# FubarStep_v11.net
KiCad netlist of a schematic drawn in EAGLE
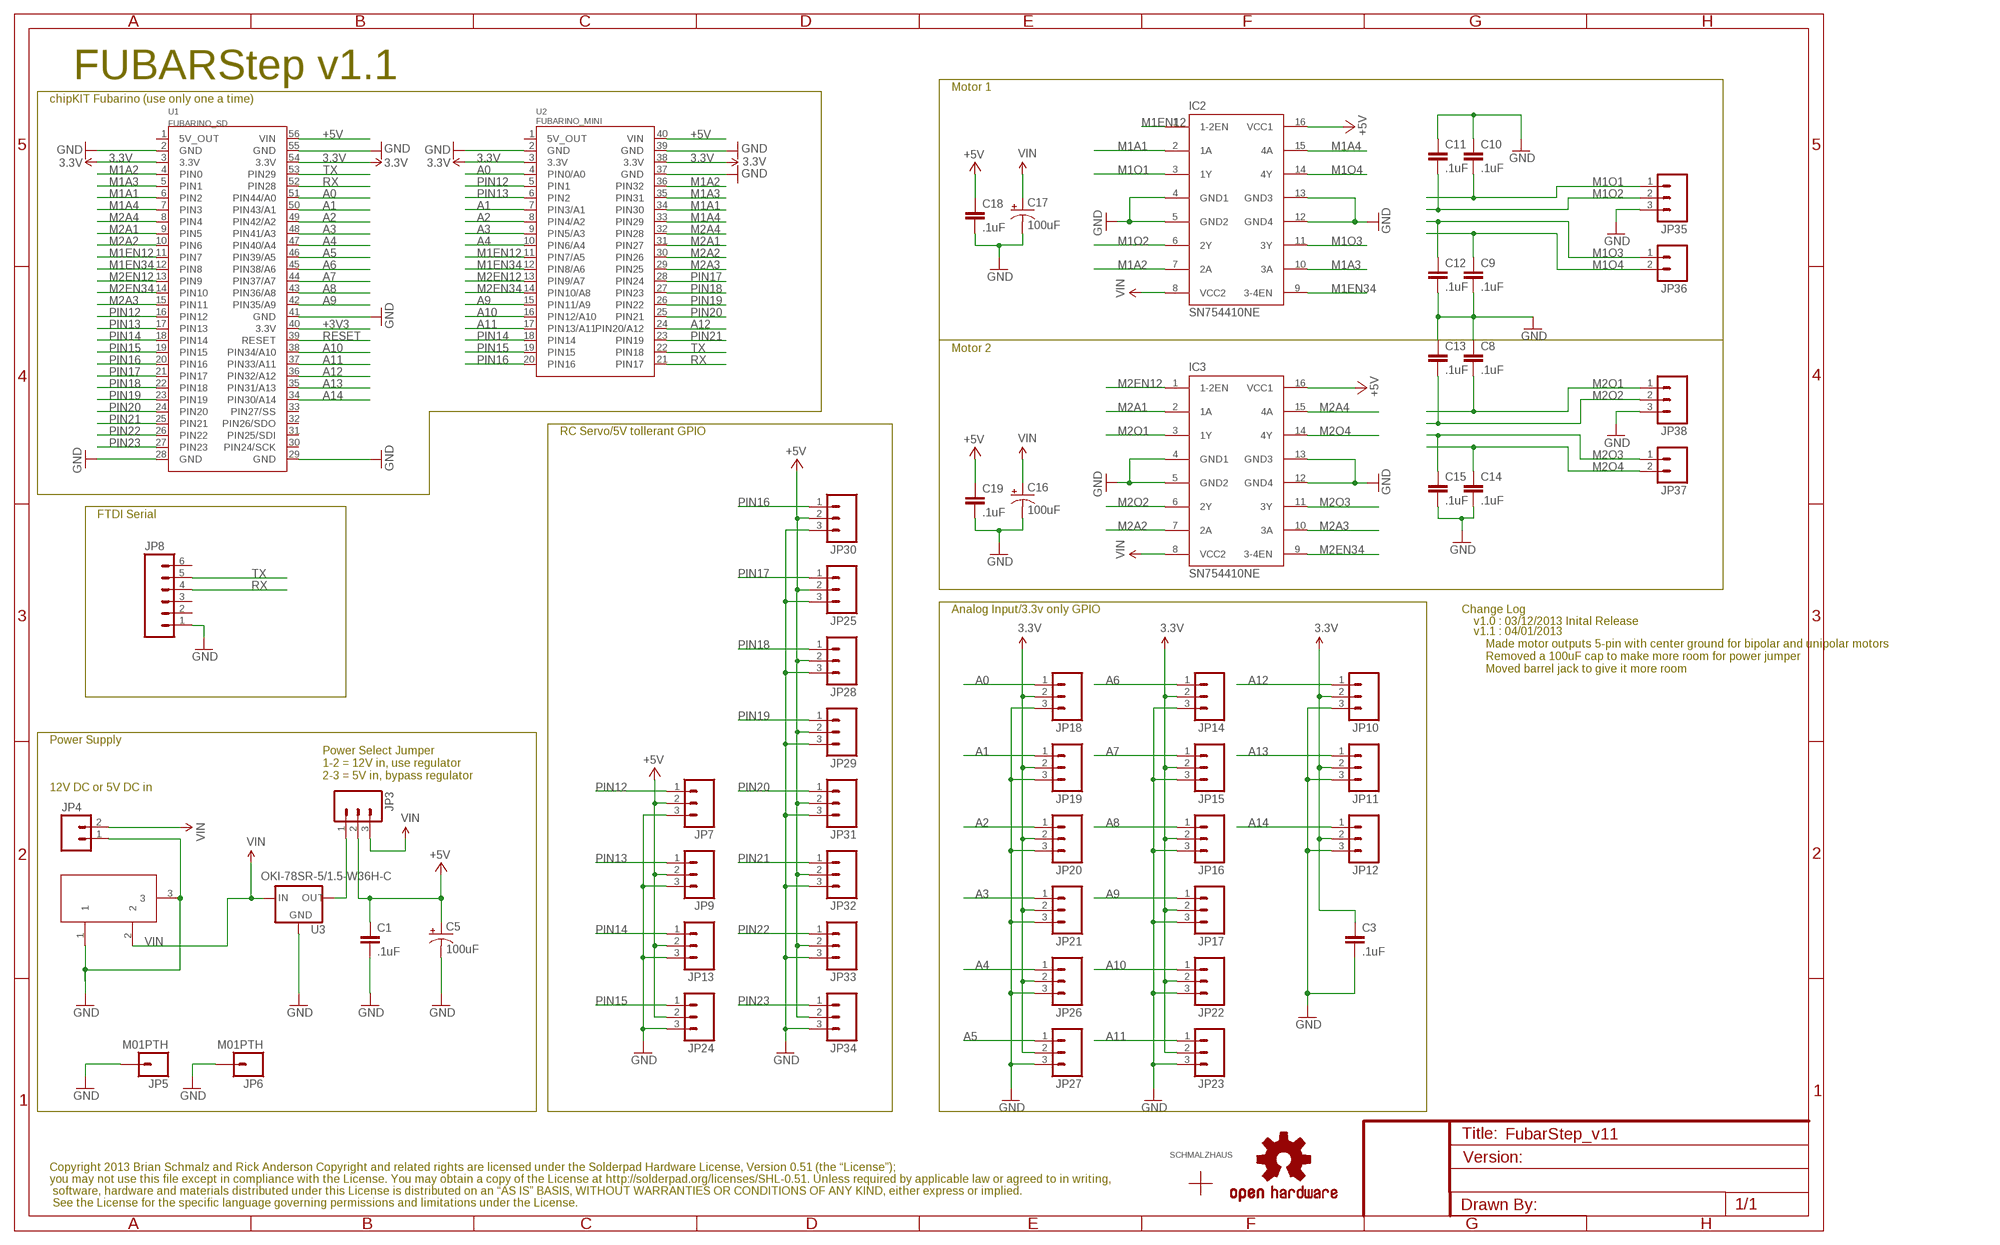
[diagram p0: schematic, sheet 1]

(export (version "E")
  (design (tool "Eeschema 10.0.6"))
  (components
    (comp (ref "C1")
      (value ".1uF")
      (footprint "eagle-import:CAP-PTH-SMALL")
      (libsource (lib "eagle-import") (part "CAPPTH"))
    )
    (comp (ref "C3")
      (value ".1uF")
      (footprint "eagle-import:CAP-PTH-SMALL")
      (libsource (lib "eagle-import") (part "CAPPTH"))
    )
    (comp (ref "C5")
      (value "100uF")
      (footprint "eagle-import:CPOL-RADIAL-100UF-25V")
      (libsource (lib "eagle-import") (part "CAP_POLPTH1"))
    )
    (comp (ref "C8")
      (value ".1uF")
      (footprint "eagle-import:CAP-PTH-SMALL")
      (libsource (lib "eagle-import") (part "CAPPTH"))
    )
    (comp (ref "C9")
      (value ".1uF")
      (footprint "eagle-import:CAP-PTH-SMALL")
      (libsource (lib "eagle-import") (part "CAPPTH"))
    )
    (comp (ref "C10")
      (value ".1uF")
      (footprint "eagle-import:CAP-PTH-SMALL")
      (libsource (lib "eagle-import") (part "CAPPTH"))
    )
    (comp (ref "C11")
      (value ".1uF")
      (footprint "eagle-import:CAP-PTH-SMALL")
      (libsource (lib "eagle-import") (part "CAPPTH"))
    )
    (comp (ref "C12")
      (value ".1uF")
      (footprint "eagle-import:CAP-PTH-SMALL")
      (libsource (lib "eagle-import") (part "CAPPTH"))
    )
    (comp (ref "C13")
      (value ".1uF")
      (footprint "eagle-import:CAP-PTH-SMALL")
      (libsource (lib "eagle-import") (part "CAPPTH"))
    )
    (comp (ref "C14")
      (value ".1uF")
      (footprint "eagle-import:CAP-PTH-SMALL")
      (libsource (lib "eagle-import") (part "CAPPTH"))
    )
    (comp (ref "C15")
      (value ".1uF")
      (footprint "eagle-import:CAP-PTH-SMALL")
      (libsource (lib "eagle-import") (part "CAPPTH"))
    )
    (comp (ref "C16")
      (value "100uF")
      (footprint "eagle-import:CPOL-RADIAL-100UF-25V")
      (libsource (lib "eagle-import") (part "CAP_POLPTH1"))
    )
    (comp (ref "C17")
      (value "100uF")
      (footprint "eagle-import:CPOL-RADIAL-100UF-25V")
      (libsource (lib "eagle-import") (part "CAP_POLPTH1"))
    )
    (comp (ref "C18")
      (value ".1uF")
      (footprint "eagle-import:CAP-PTH-SMALL")
      (libsource (lib "eagle-import") (part "CAPPTH"))
    )
    (comp (ref "C19")
      (value ".1uF")
      (footprint "eagle-import:CAP-PTH-SMALL")
      (libsource (lib "eagle-import") (part "CAPPTH"))
    )
    (comp (ref "IC2")
      (value "SN754410NE")
      (footprint "eagle-import:DIL16")
      (fields (field (name "MF") "Arrow Electronics") (field (name "MPN") "L293E"))
      (libsource (lib "eagle-import") (part "L293E"))
    )
    (comp (ref "IC3")
      (value "SN754410NE")
      (footprint "eagle-import:DIL16")
      (fields (field (name "MF") "Arrow Electronics") (field (name "MPN") "L293E"))
      (libsource (lib "eagle-import") (part "L293E"))
    )
    (comp (ref "JP3")
      (value "M03PTH")
      (footprint "eagle-import:1X03")
      (libsource (lib "eagle-import") (part "M03PTH"))
    )
    (comp (ref "JP4")
      (value "M023.5MM")
      (footprint "eagle-import:SCREWTERMINAL-3.5MM-2")
      (libsource (lib "eagle-import") (part "M023.5MM"))
    )
    (comp (ref "JP5")
      (value "M01PTH")
      (footprint "eagle-import:1X01")
      (libsource (lib "eagle-import") (part "M01PTH"))
    )
    (comp (ref "JP6")
      (value "M01PTH")
      (footprint "eagle-import:1X01")
      (libsource (lib "eagle-import") (part "M01PTH"))
    )
    (comp (ref "JP7")
      (value "M03PTH")
      (footprint "eagle-import:1X03")
      (libsource (lib "eagle-import") (part "M03PTH"))
    )
    (comp (ref "JP8")
      (value "M06LOCK")
      (footprint "eagle-import:1X06_LOCK")
      (libsource (lib "eagle-import") (part "M06LOCK"))
    )
    (comp (ref "JP9")
      (value "M03PTH")
      (footprint "eagle-import:1X03")
      (libsource (lib "eagle-import") (part "M03PTH"))
    )
    (comp (ref "JP10")
      (value "M03PTH")
      (footprint "eagle-import:1X03")
      (libsource (lib "eagle-import") (part "M03PTH"))
    )
    (comp (ref "JP11")
      (value "M03PTH")
      (footprint "eagle-import:1X03")
      (libsource (lib "eagle-import") (part "M03PTH"))
    )
    (comp (ref "JP12")
      (value "M03PTH")
      (footprint "eagle-import:1X03")
      (libsource (lib "eagle-import") (part "M03PTH"))
    )
    (comp (ref "JP13")
      (value "M03PTH")
      (footprint "eagle-import:1X03")
      (libsource (lib "eagle-import") (part "M03PTH"))
    )
    (comp (ref "JP14")
      (value "M03PTH")
      (footprint "eagle-import:1X03")
      (libsource (lib "eagle-import") (part "M03PTH"))
    )
    (comp (ref "JP15")
      (value "M03PTH")
      (footprint "eagle-import:1X03")
      (libsource (lib "eagle-import") (part "M03PTH"))
    )
    (comp (ref "JP16")
      (value "M03PTH")
      (footprint "eagle-import:1X03")
      (libsource (lib "eagle-import") (part "M03PTH"))
    )
    (comp (ref "JP17")
      (value "M03PTH")
      (footprint "eagle-import:1X03")
      (libsource (lib "eagle-import") (part "M03PTH"))
    )
    (comp (ref "JP18")
      (value "M03PTH")
      (footprint "eagle-import:1X03")
      (libsource (lib "eagle-import") (part "M03PTH"))
    )
    (comp (ref "JP19")
      (value "M03PTH")
      (footprint "eagle-import:1X03")
      (libsource (lib "eagle-import") (part "M03PTH"))
    )
    (comp (ref "JP20")
      (value "M03PTH")
      (footprint "eagle-import:1X03")
      (libsource (lib "eagle-import") (part "M03PTH"))
    )
    (comp (ref "JP21")
      (value "M03PTH")
      (footprint "eagle-import:1X03")
      (libsource (lib "eagle-import") (part "M03PTH"))
    )
    (comp (ref "JP22")
      (value "M03PTH")
      (footprint "eagle-import:1X03")
      (libsource (lib "eagle-import") (part "M03PTH"))
    )
    (comp (ref "JP23")
      (value "M03PTH")
      (footprint "eagle-import:1X03")
      (libsource (lib "eagle-import") (part "M03PTH"))
    )
    (comp (ref "JP24")
      (value "M03PTH")
      (footprint "eagle-import:1X03")
      (libsource (lib "eagle-import") (part "M03PTH"))
    )
    (comp (ref "JP25")
      (value "M03PTH")
      (footprint "eagle-import:1X03")
      (libsource (lib "eagle-import") (part "M03PTH"))
    )
    (comp (ref "JP26")
      (value "M03PTH")
      (footprint "eagle-import:1X03")
      (libsource (lib "eagle-import") (part "M03PTH"))
    )
    (comp (ref "JP27")
      (value "M03PTH")
      (footprint "eagle-import:1X03")
      (libsource (lib "eagle-import") (part "M03PTH"))
    )
    (comp (ref "JP28")
      (value "M03PTH")
      (footprint "eagle-import:1X03")
      (libsource (lib "eagle-import") (part "M03PTH"))
    )
    (comp (ref "JP29")
      (value "M03PTH")
      (footprint "eagle-import:1X03")
      (libsource (lib "eagle-import") (part "M03PTH"))
    )
    (comp (ref "JP30")
      (value "M03PTH")
      (footprint "eagle-import:1X03")
      (libsource (lib "eagle-import") (part "M03PTH"))
    )
    (comp (ref "JP31")
      (value "M03PTH")
      (footprint "eagle-import:1X03")
      (libsource (lib "eagle-import") (part "M03PTH"))
    )
    (comp (ref "JP32")
      (value "M03PTH")
      (footprint "eagle-import:1X03")
      (libsource (lib "eagle-import") (part "M03PTH"))
    )
    (comp (ref "JP33")
      (value "M03PTH")
      (footprint "eagle-import:1X03")
      (libsource (lib "eagle-import") (part "M03PTH"))
    )
    (comp (ref "JP34")
      (value "M03PTH")
      (footprint "eagle-import:1X03")
      (libsource (lib "eagle-import") (part "M03PTH"))
    )
    (comp (ref "JP35")
      (value "M03SCREW")
      (footprint "eagle-import:SCREWTERMINAL-3.5MM-3")
      (libsource (lib "eagle-import") (part "M03SCREW"))
    )
    (comp (ref "JP36")
      (value "M023.5MM")
      (footprint "eagle-import:SCREWTERMINAL-3.5MM-2")
      (libsource (lib "eagle-import") (part "M023.5MM"))
    )
    (comp (ref "JP37")
      (value "M023.5MM")
      (footprint "eagle-import:SCREWTERMINAL-3.5MM-2")
      (libsource (lib "eagle-import") (part "M023.5MM"))
    )
    (comp (ref "JP38")
      (value "M03SCREW")
      (footprint "eagle-import:SCREWTERMINAL-3.5MM-3")
      (libsource (lib "eagle-import") (part "M03SCREW"))
    )
    (comp (ref "LOGO1")
      (value "OSHW-LOGOM")
      (footprint "eagle-import:OSHW-LOGO-M")
      (libsource (lib "eagle-import") (part "OSHW-LOGOM"))
    )
    (comp (ref "U$1")
      (value "SCHMALZHAUSSCHMALZHAUS_SMALL")
      (footprint "eagle-import:SCHMALZHAUS_SMALL")
      (libsource (lib "eagle-import") (part "SCHMALZHAUSSCHMALZHAUS_SMALL"))
    )
    (comp (ref "U1")
      (value "FUBARINO_SD")
      (footprint "eagle-import:FUBARINO_SD")
      (libsource (lib "eagle-import") (part "FUBARINO_SD"))
    )
    (comp (ref "U2")
      (value "FUBARINO_MINI")
      (footprint "eagle-import:FUBARINO_MINI")
      (libsource (lib "eagle-import") (part "FUBARINO_MINI"))
    )
    (comp (ref "U3")
      (value "OKI-78SR-5/1.5-W36H-C")
      (footprint "eagle-import:TO220-IGO")
      (libsource (lib "eagle-import") (part "V_REG_78XXSINK"))
    )
    (comp (ref "X1")
      (value "DC21MMX")
      (footprint "eagle-import:DC-21MM")
      (libsource (lib "eagle-import") (part "DC21MMX"))
    )
  )
  (nets
    (net (code "1") (name "+5V") (class "Default")
      (node (ref "C1") (pin "1") (pinfunction "1_1") (pintype "passive"))
      (node (ref "C18") (pin "1") (pinfunction "1_1") (pintype "passive"))
      (node (ref "C19") (pin "1") (pinfunction "1_1") (pintype "passive"))
      (node (ref "C5") (pin "1") (pinfunction "+_1") (pintype "passive"))
      (node (ref "IC2") (pin "16") (pinfunction "VCC1_16") (pintype "power_in"))
      (node (ref "IC3") (pin "16") (pinfunction "VCC1_16") (pintype "power_in"))
      (node (ref "JP13") (pin "2") (pinfunction "2_2") (pintype "passive"))
      (node (ref "JP24") (pin "2") (pinfunction "2_2") (pintype "passive"))
      (node (ref "JP25") (pin "2") (pinfunction "2_2") (pintype "passive"))
      (node (ref "JP28") (pin "2") (pinfunction "2_2") (pintype "passive"))
      (node (ref "JP29") (pin "2") (pinfunction "2_2") (pintype "passive"))
      (node (ref "JP3") (pin "2") (pinfunction "2_2") (pintype "passive"))
      (node (ref "JP30") (pin "2") (pinfunction "2_2") (pintype "passive"))
      (node (ref "JP31") (pin "2") (pinfunction "2_2") (pintype "passive"))
      (node (ref "JP32") (pin "2") (pinfunction "2_2") (pintype "passive"))
      (node (ref "JP33") (pin "2") (pinfunction "2_2") (pintype "passive"))
      (node (ref "JP34") (pin "2") (pinfunction "2_2") (pintype "passive"))
      (node (ref "JP7") (pin "2") (pinfunction "2_2") (pintype "passive"))
      (node (ref "JP9") (pin "2") (pinfunction "2_2") (pintype "passive"))
      (node (ref "U1") (pin "56") (pinfunction "VIN_56") (pintype "bidirectional"))
      (node (ref "U2") (pin "40") (pinfunction "VIN_40") (pintype "bidirectional"))
    )
    (net (code "2") (name "/+3V3") (class "Default")
      (node (ref "U1") (pin "40") (pinfunction "3.3V_40") (pintype "bidirectional"))
    )
    (net (code "3") (name "/A0") (class "Default")
      (node (ref "JP18") (pin "1") (pinfunction "1_1") (pintype "passive"))
      (node (ref "U1") (pin "51") (pinfunction "PIN44/A0_51") (pintype "bidirectional"))
      (node (ref "U2") (pin "4") (pinfunction "PIN0/A0_4") (pintype "bidirectional"))
    )
    (net (code "4") (name "/A1") (class "Default")
      (node (ref "JP19") (pin "1") (pinfunction "1_1") (pintype "passive"))
      (node (ref "U1") (pin "50") (pinfunction "PIN43/A1_50") (pintype "bidirectional"))
      (node (ref "U2") (pin "7") (pinfunction "PIN3/A1_7") (pintype "bidirectional"))
    )
    (net (code "5") (name "/A2") (class "Default")
      (node (ref "JP20") (pin "1") (pinfunction "1_1") (pintype "passive"))
      (node (ref "U1") (pin "49") (pinfunction "PIN42/A2_49") (pintype "bidirectional"))
      (node (ref "U2") (pin "8") (pinfunction "PIN4/A2_8") (pintype "bidirectional"))
    )
    (net (code "6") (name "/A3") (class "Default")
      (node (ref "JP21") (pin "1") (pinfunction "1_1") (pintype "passive"))
      (node (ref "U1") (pin "48") (pinfunction "PIN41/A3_48") (pintype "bidirectional"))
      (node (ref "U2") (pin "9") (pinfunction "PIN5/A3_9") (pintype "bidirectional"))
    )
    (net (code "7") (name "/A4") (class "Default")
      (node (ref "JP26") (pin "1") (pinfunction "1_1") (pintype "passive"))
      (node (ref "U1") (pin "47") (pinfunction "PIN40/A4_47") (pintype "bidirectional"))
      (node (ref "U2") (pin "10") (pinfunction "PIN6/A4_10") (pintype "bidirectional"))
    )
    (net (code "8") (name "/A5") (class "Default")
      (node (ref "JP27") (pin "1") (pinfunction "1_1") (pintype "passive"))
      (node (ref "U1") (pin "46") (pinfunction "PIN39/A5_46") (pintype "bidirectional"))
    )
    (net (code "9") (name "/A6") (class "Default")
      (node (ref "JP14") (pin "1") (pinfunction "1_1") (pintype "passive"))
      (node (ref "U1") (pin "45") (pinfunction "PIN38/A6_45") (pintype "bidirectional"))
    )
    (net (code "10") (name "/A7") (class "Default")
      (node (ref "JP15") (pin "1") (pinfunction "1_1") (pintype "passive"))
      (node (ref "U1") (pin "44") (pinfunction "PIN37/A7_44") (pintype "bidirectional"))
    )
    (net (code "11") (name "/A8") (class "Default")
      (node (ref "JP16") (pin "1") (pinfunction "1_1") (pintype "passive"))
      (node (ref "U1") (pin "43") (pinfunction "PIN36/A8_43") (pintype "bidirectional"))
    )
    (net (code "12") (name "/A9") (class "Default")
      (node (ref "JP17") (pin "1") (pinfunction "1_1") (pintype "passive"))
      (node (ref "U1") (pin "42") (pinfunction "PIN35/A9_42") (pintype "bidirectional"))
      (node (ref "U2") (pin "15") (pinfunction "PIN11/A9_15") (pintype "bidirectional"))
    )
    (net (code "13") (name "/A10") (class "Default")
      (node (ref "JP22") (pin "1") (pinfunction "1_1") (pintype "passive"))
      (node (ref "U1") (pin "38") (pinfunction "PIN34/A10_38") (pintype "bidirectional"))
      (node (ref "U2") (pin "16") (pinfunction "PIN12/A10_16") (pintype "bidirectional"))
    )
    (net (code "14") (name "/A11") (class "Default")
      (node (ref "JP23") (pin "1") (pinfunction "1_1") (pintype "passive"))
      (node (ref "U1") (pin "37") (pinfunction "PIN33/A11_37") (pintype "bidirectional"))
      (node (ref "U2") (pin "17") (pinfunction "PIN13/A11_17") (pintype "bidirectional"))
    )
    (net (code "15") (name "/A12") (class "Default")
      (node (ref "JP10") (pin "1") (pinfunction "1_1") (pintype "passive"))
      (node (ref "U1") (pin "36") (pinfunction "PIN32/A12_36") (pintype "bidirectional"))
      (node (ref "U2") (pin "24") (pinfunction "PIN20/A12_24") (pintype "bidirectional"))
    )
    (net (code "16") (name "/A13") (class "Default")
      (node (ref "JP11") (pin "1") (pinfunction "1_1") (pintype "passive"))
      (node (ref "U1") (pin "35") (pinfunction "PIN31/A13_35") (pintype "bidirectional"))
    )
    (net (code "17") (name "/A14") (class "Default")
      (node (ref "JP12") (pin "1") (pinfunction "1_1") (pintype "passive"))
      (node (ref "U1") (pin "34") (pinfunction "PIN30/A14_34") (pintype "bidirectional"))
    )
    (net (code "18") (name "/M1A1") (class "Default")
      (node (ref "IC2") (pin "2") (pinfunction "1A_2") (pintype "input"))
      (node (ref "U1") (pin "6") (pinfunction "PIN2_6") (pintype "bidirectional"))
      (node (ref "U2") (pin "34") (pinfunction "PIN30_34") (pintype "bidirectional"))
    )
    (net (code "19") (name "/M1A2") (class "Default")
      (node (ref "IC2") (pin "7") (pinfunction "2A_7") (pintype "input"))
      (node (ref "U1") (pin "4") (pinfunction "PIN0_4") (pintype "bidirectional"))
      (node (ref "U2") (pin "36") (pinfunction "PIN32_36") (pintype "bidirectional"))
    )
    (net (code "20") (name "/M1A3") (class "Default")
      (node (ref "IC2") (pin "10") (pinfunction "3A_10") (pintype "input"))
      (node (ref "U1") (pin "5") (pinfunction "PIN1_5") (pintype "bidirectional"))
      (node (ref "U2") (pin "35") (pinfunction "PIN31_35") (pintype "bidirectional"))
    )
    (net (code "21") (name "/M1A4") (class "Default")
      (node (ref "IC2") (pin "15") (pinfunction "4A_15") (pintype "input"))
      (node (ref "U1") (pin "7") (pinfunction "PIN3_7") (pintype "bidirectional"))
      (node (ref "U2") (pin "33") (pinfunction "PIN29_33") (pintype "bidirectional"))
    )
    (net (code "22") (name "/M1EN12") (class "Default")
      (node (ref "IC2") (pin "1") (pinfunction "1-2EN_1") (pintype "input"))
      (node (ref "U1") (pin "11") (pinfunction "PIN7_11") (pintype "bidirectional"))
      (node (ref "U2") (pin "11") (pinfunction "PIN7/A5_11") (pintype "bidirectional"))
    )
    (net (code "23") (name "/M1EN34") (class "Default")
      (node (ref "IC2") (pin "9") (pinfunction "3-4EN_9") (pintype "input"))
      (node (ref "U1") (pin "12") (pinfunction "PIN8_12") (pintype "bidirectional"))
      (node (ref "U2") (pin "12") (pinfunction "PIN8/A6_12") (pintype "bidirectional"))
    )
    (net (code "24") (name "/M1O1") (class "Default")
      (node (ref "C10") (pin "2") (pinfunction "2_2") (pintype "passive"))
      (node (ref "IC2") (pin "3") (pinfunction "1Y_3") (pintype "output"))
      (node (ref "JP35") (pin "1") (pinfunction "1_1") (pintype "passive"))
    )
    (net (code "25") (name "/M1O2") (class "Default")
      (node (ref "C11") (pin "2") (pinfunction "2_2") (pintype "passive"))
      (node (ref "IC2") (pin "6") (pinfunction "2Y_6") (pintype "output"))
      (node (ref "JP35") (pin "2") (pinfunction "2_2") (pintype "passive"))
    )
    (net (code "26") (name "/M1O3") (class "Default")
      (node (ref "C12") (pin "1") (pinfunction "1_1") (pintype "passive"))
      (node (ref "IC2") (pin "11") (pinfunction "3Y_11") (pintype "output"))
      (node (ref "JP36") (pin "1") (pinfunction "1_1") (pintype "passive"))
    )
    (net (code "27") (name "/M1O4") (class "Default")
      (node (ref "C9") (pin "1") (pinfunction "1_1") (pintype "passive"))
      (node (ref "IC2") (pin "14") (pinfunction "4Y_14") (pintype "output"))
      (node (ref "JP36") (pin "2") (pinfunction "2_2") (pintype "passive"))
    )
    (net (code "28") (name "/M2A1") (class "Default")
      (node (ref "IC3") (pin "2") (pinfunction "1A_2") (pintype "input"))
      (node (ref "U1") (pin "9") (pinfunction "PIN5_9") (pintype "bidirectional"))
      (node (ref "U2") (pin "31") (pinfunction "PIN27_31") (pintype "bidirectional"))
    )
    (net (code "29") (name "/M2A2") (class "Default")
      (node (ref "IC3") (pin "7") (pinfunction "2A_7") (pintype "input"))
      (node (ref "U1") (pin "10") (pinfunction "PIN6_10") (pintype "bidirectional"))
      (node (ref "U2") (pin "30") (pinfunction "PIN26_30") (pintype "bidirectional"))
    )
    (net (code "30") (name "/M2A3") (class "Default")
      (node (ref "IC3") (pin "10") (pinfunction "3A_10") (pintype "input"))
      (node (ref "U1") (pin "15") (pinfunction "PIN11_15") (pintype "bidirectional"))
      (node (ref "U2") (pin "29") (pinfunction "PIN25_29") (pintype "bidirectional"))
    )
    (net (code "31") (name "/M2A4") (class "Default")
      (node (ref "IC3") (pin "15") (pinfunction "4A_15") (pintype "input"))
      (node (ref "U1") (pin "8") (pinfunction "PIN4_8") (pintype "bidirectional"))
      (node (ref "U2") (pin "32") (pinfunction "PIN28_32") (pintype "bidirectional"))
    )
    (net (code "32") (name "/M2EN12") (class "Default")
      (node (ref "IC3") (pin "1") (pinfunction "1-2EN_1") (pintype "input"))
      (node (ref "U1") (pin "13") (pinfunction "PIN9_13") (pintype "bidirectional"))
      (node (ref "U2") (pin "13") (pinfunction "PIN9/A7_13") (pintype "bidirectional"))
    )
    (net (code "33") (name "/M2EN34") (class "Default")
      (node (ref "IC3") (pin "9") (pinfunction "3-4EN_9") (pintype "input"))
      (node (ref "U1") (pin "14") (pinfunction "PIN10_14") (pintype "bidirectional"))
      (node (ref "U2") (pin "14") (pinfunction "PIN10/A8_14") (pintype "bidirectional"))
    )
    (net (code "34") (name "/M2O1") (class "Default")
      (node (ref "C8") (pin "2") (pinfunction "2_2") (pintype "passive"))
      (node (ref "IC3") (pin "3") (pinfunction "1Y_3") (pintype "output"))
      (node (ref "JP38") (pin "1") (pinfunction "1_1") (pintype "passive"))
    )
    (net (code "35") (name "/M2O2") (class "Default")
      (node (ref "C13") (pin "2") (pinfunction "2_2") (pintype "passive"))
      (node (ref "IC3") (pin "6") (pinfunction "2Y_6") (pintype "output"))
      (node (ref "JP38") (pin "2") (pinfunction "2_2") (pintype "passive"))
    )
    (net (code "36") (name "/M2O3") (class "Default")
      (node (ref "C15") (pin "1") (pinfunction "1_1") (pintype "passive"))
      (node (ref "IC3") (pin "11") (pinfunction "3Y_11") (pintype "output"))
      (node (ref "JP37") (pin "1") (pinfunction "1_1") (pintype "passive"))
    )
    (net (code "37") (name "/M2O4") (class "Default")
      (node (ref "C14") (pin "1") (pinfunction "1_1") (pintype "passive"))
      (node (ref "IC3") (pin "14") (pinfunction "4Y_14") (pintype "output"))
      (node (ref "JP37") (pin "2") (pinfunction "2_2") (pintype "passive"))
    )
    (net (code "38") (name "/PIN12") (class "Default")
      (node (ref "JP7") (pin "1") (pinfunction "1_1") (pintype "passive"))
      (node (ref "U1") (pin "16") (pinfunction "PIN12_16") (pintype "bidirectional"))
      (node (ref "U2") (pin "5") (pinfunction "PIN1_5") (pintype "bidirectional"))
    )
    (net (code "39") (name "/PIN13") (class "Default")
      (node (ref "JP9") (pin "1") (pinfunction "1_1") (pintype "passive"))
      (node (ref "U1") (pin "17") (pinfunction "PIN13_17") (pintype "bidirectional"))
      (node (ref "U2") (pin "6") (pinfunction "PIN2_6") (pintype "bidirectional"))
    )
    (net (code "40") (name "/PIN14") (class "Default")
      (node (ref "JP13") (pin "1") (pinfunction "1_1") (pintype "passive"))
      (node (ref "U1") (pin "18") (pinfunction "PIN14_18") (pintype "bidirectional"))
      (node (ref "U2") (pin "18") (pinfunction "PIN14_18") (pintype "bidirectional"))
    )
    (net (code "41") (name "/PIN15") (class "Default")
      (node (ref "JP24") (pin "1") (pinfunction "1_1") (pintype "passive"))
      (node (ref "U1") (pin "19") (pinfunction "PIN15_19") (pintype "bidirectional"))
      (node (ref "U2") (pin "19") (pinfunction "PIN15_19") (pintype "bidirectional"))
    )
    (net (code "42") (name "/PIN16") (class "Default")
      (node (ref "JP30") (pin "1") (pinfunction "1_1") (pintype "passive"))
      (node (ref "U1") (pin "20") (pinfunction "PIN16_20") (pintype "bidirectional"))
      (node (ref "U2") (pin "20") (pinfunction "PIN16_20") (pintype "bidirectional"))
    )
    (net (code "43") (name "/PIN17") (class "Default")
      (node (ref "JP25") (pin "1") (pinfunction "1_1") (pintype "passive"))
      (node (ref "U1") (pin "21") (pinfunction "PIN17_21") (pintype "bidirectional"))
      (node (ref "U2") (pin "28") (pinfunction "PIN24_28") (pintype "bidirectional"))
    )
    (net (code "44") (name "/PIN18") (class "Default")
      (node (ref "JP28") (pin "1") (pinfunction "1_1") (pintype "passive"))
      (node (ref "U1") (pin "22") (pinfunction "PIN18_22") (pintype "bidirectional"))
      (node (ref "U2") (pin "27") (pinfunction "PIN23_27") (pintype "bidirectional"))
    )
    (net (code "45") (name "/PIN19") (class "Default")
      (node (ref "JP29") (pin "1") (pinfunction "1_1") (pintype "passive"))
      (node (ref "U1") (pin "23") (pinfunction "PIN19_23") (pintype "bidirectional"))
      (node (ref "U2") (pin "26") (pinfunction "PIN22_26") (pintype "bidirectional"))
    )
    (net (code "46") (name "/PIN20") (class "Default")
      (node (ref "JP31") (pin "1") (pinfunction "1_1") (pintype "passive"))
      (node (ref "U1") (pin "24") (pinfunction "PIN20_24") (pintype "bidirectional"))
      (node (ref "U2") (pin "25") (pinfunction "PIN21_25") (pintype "bidirectional"))
    )
    (net (code "47") (name "/PIN21") (class "Default")
      (node (ref "JP32") (pin "1") (pinfunction "1_1") (pintype "passive"))
      (node (ref "U1") (pin "25") (pinfunction "PIN21_25") (pintype "bidirectional"))
      (node (ref "U2") (pin "23") (pinfunction "PIN19_23") (pintype "bidirectional"))
    )
    (net (code "48") (name "/PIN22") (class "Default")
      (node (ref "JP33") (pin "1") (pinfunction "1_1") (pintype "passive"))
      (node (ref "U1") (pin "26") (pinfunction "PIN22_26") (pintype "bidirectional"))
    )
    (net (code "49") (name "/PIN23") (class "Default")
      (node (ref "JP34") (pin "1") (pinfunction "1_1") (pintype "passive"))
      (node (ref "U1") (pin "27") (pinfunction "PIN23_27") (pintype "bidirectional"))
    )
    (net (code "50") (name "/RESET") (class "Default")
      (node (ref "U1") (pin "39") (pinfunction "RESET_39") (pintype "bidirectional"))
    )
    (net (code "51") (name "/RX") (class "Default")
      (node (ref "JP8") (pin "4") (pinfunction "4_4") (pintype "passive"))
      (node (ref "U1") (pin "52") (pinfunction "PIN28_52") (pintype "bidirectional"))
      (node (ref "U2") (pin "21") (pinfunction "PIN17_21") (pintype "bidirectional"))
    )
    (net (code "52") (name "/TX") (class "Default")
      (node (ref "JP8") (pin "5") (pinfunction "5_5") (pintype "passive"))
      (node (ref "U1") (pin "53") (pinfunction "PIN29_53") (pintype "bidirectional"))
      (node (ref "U2") (pin "22") (pinfunction "PIN18_22") (pintype "bidirectional"))
    )
    (net (code "53") (name "3.3V") (class "Default")
      (node (ref "C3") (pin "1") (pinfunction "1_1") (pintype "passive"))
      (node (ref "JP10") (pin "2") (pinfunction "2_2") (pintype "passive"))
      (node (ref "JP11") (pin "2") (pinfunction "2_2") (pintype "passive"))
      (node (ref "JP12") (pin "2") (pinfunction "2_2") (pintype "passive"))
      (node (ref "JP14") (pin "2") (pinfunction "2_2") (pintype "passive"))
      (node (ref "JP15") (pin "2") (pinfunction "2_2") (pintype "passive"))
      (node (ref "JP16") (pin "2") (pinfunction "2_2") (pintype "passive"))
      (node (ref "JP17") (pin "2") (pinfunction "2_2") (pintype "passive"))
      (node (ref "JP18") (pin "2") (pinfunction "2_2") (pintype "passive"))
      (node (ref "JP19") (pin "2") (pinfunction "2_2") (pintype "passive"))
      (node (ref "JP20") (pin "2") (pinfunction "2_2") (pintype "passive"))
      (node (ref "JP21") (pin "2") (pinfunction "2_2") (pintype "passive"))
      (node (ref "JP22") (pin "2") (pinfunction "2_2") (pintype "passive"))
      (node (ref "JP23") (pin "2") (pinfunction "2_2") (pintype "passive"))
      (node (ref "JP26") (pin "2") (pinfunction "2_2") (pintype "passive"))
      (node (ref "JP27") (pin "2") (pinfunction "2_2") (pintype "passive"))
      (node (ref "U1") (pin "3") (pinfunction "3.3V_3") (pintype "bidirectional"))
      (node (ref "U1") (pin "54") (pinfunction "3.3V_54") (pintype "bidirectional"))
      (node (ref "U2") (pin "3") (pinfunction "3.3V_3") (pintype "bidirectional"))
      (node (ref "U2") (pin "38") (pinfunction "3.3V_38") (pintype "bidirectional"))
    )
    (net (code "54") (name "GND") (class "Default")
      (node (ref "C1") (pin "2") (pinfunction "2_2") (pintype "passive"))
      (node (ref "C10") (pin "1") (pinfunction "1_1") (pintype "passive"))
      (node (ref "C11") (pin "1") (pinfunction "1_1") (pintype "passive"))
      (node (ref "C12") (pin "2") (pinfunction "2_2") (pintype "passive"))
      (node (ref "C13") (pin "1") (pinfunction "1_1") (pintype "passive"))
      (node (ref "C14") (pin "2") (pinfunction "2_2") (pintype "passive"))
      (node (ref "C15") (pin "2") (pinfunction "2_2") (pintype "passive"))
      (node (ref "C16") (pin "2") (pinfunction "-_2") (pintype "passive"))
      (node (ref "C17") (pin "2") (pinfunction "-_2") (pintype "passive"))
      (node (ref "C18") (pin "2") (pinfunction "2_2") (pintype "passive"))
      (node (ref "C19") (pin "2") (pinfunction "2_2") (pintype "passive"))
      (node (ref "C3") (pin "2") (pinfunction "2_2") (pintype "passive"))
      (node (ref "C5") (pin "2") (pinfunction "-_2") (pintype "passive"))
      (node (ref "C8") (pin "1") (pinfunction "1_1") (pintype "passive"))
      (node (ref "C9") (pin "2") (pinfunction "2_2") (pintype "passive"))
      (node (ref "IC2") (pin "12") (pinfunction "GND4_12") (pintype "power_in"))
      (node (ref "IC2") (pin "13") (pinfunction "GND3_13") (pintype "power_in"))
      (node (ref "IC2") (pin "4") (pinfunction "GND1_4") (pintype "power_in"))
      (node (ref "IC2") (pin "5") (pinfunction "GND2_5") (pintype "power_in"))
      (node (ref "IC3") (pin "12") (pinfunction "GND4_12") (pintype "power_in"))
      (node (ref "IC3") (pin "13") (pinfunction "GND3_13") (pintype "power_in"))
      (node (ref "IC3") (pin "4") (pinfunction "GND1_4") (pintype "power_in"))
      (node (ref "IC3") (pin "5") (pinfunction "GND2_5") (pintype "power_in"))
      (node (ref "JP10") (pin "3") (pinfunction "3_3") (pintype "passive"))
      (node (ref "JP11") (pin "3") (pinfunction "3_3") (pintype "passive"))
      (node (ref "JP12") (pin "3") (pinfunction "3_3") (pintype "passive"))
      (node (ref "JP13") (pin "3") (pinfunction "3_3") (pintype "passive"))
      (node (ref "JP14") (pin "3") (pinfunction "3_3") (pintype "passive"))
      (node (ref "JP15") (pin "3") (pinfunction "3_3") (pintype "passive"))
      (node (ref "JP16") (pin "3") (pinfunction "3_3") (pintype "passive"))
      (node (ref "JP17") (pin "3") (pinfunction "3_3") (pintype "passive"))
      (node (ref "JP18") (pin "3") (pinfunction "3_3") (pintype "passive"))
      (node (ref "JP19") (pin "3") (pinfunction "3_3") (pintype "passive"))
      (node (ref "JP20") (pin "3") (pinfunction "3_3") (pintype "passive"))
      (node (ref "JP21") (pin "3") (pinfunction "3_3") (pintype "passive"))
      (node (ref "JP22") (pin "3") (pinfunction "3_3") (pintype "passive"))
      (node (ref "JP23") (pin "3") (pinfunction "3_3") (pintype "passive"))
      (node (ref "JP24") (pin "3") (pinfunction "3_3") (pintype "passive"))
      (node (ref "JP25") (pin "3") (pinfunction "3_3") (pintype "passive"))
      (node (ref "JP26") (pin "3") (pinfunction "3_3") (pintype "passive"))
      (node (ref "JP27") (pin "3") (pinfunction "3_3") (pintype "passive"))
      (node (ref "JP28") (pin "3") (pinfunction "3_3") (pintype "passive"))
      (node (ref "JP29") (pin "3") (pinfunction "3_3") (pintype "passive"))
      (node (ref "JP30") (pin "3") (pinfunction "3_3") (pintype "passive"))
      (node (ref "JP31") (pin "3") (pinfunction "3_3") (pintype "passive"))
      (node (ref "JP32") (pin "3") (pinfunction "3_3") (pintype "passive"))
      (node (ref "JP33") (pin "3") (pinfunction "3_3") (pintype "passive"))
      (node (ref "JP34") (pin "3") (pinfunction "3_3") (pintype "passive"))
      (node (ref "JP35") (pin "3") (pinfunction "3_3") (pintype "passive"))
      (node (ref "JP38") (pin "3") (pinfunction "3_3") (pintype "passive"))
      (node (ref "JP4") (pin "1") (pinfunction "1_1") (pintype "passive"))
      (node (ref "JP5") (pin "1") (pinfunction "1_1") (pintype "passive"))
      (node (ref "JP6") (pin "1") (pinfunction "1_1") (pintype "passive"))
      (node (ref "JP7") (pin "3") (pinfunction "3_3") (pintype "passive"))
      (node (ref "JP8") (pin "1") (pinfunction "1_1") (pintype "passive"))
      (node (ref "JP9") (pin "3") (pinfunction "3_3") (pintype "passive"))
      (node (ref "U1") (pin "2") (pinfunction "GND_2") (pintype "bidirectional"))
      (node (ref "U1") (pin "28") (pinfunction "GND_28") (pintype "bidirectional"))
      (node (ref "U1") (pin "29") (pinfunction "GND_29") (pintype "bidirectional"))
      (node (ref "U1") (pin "41") (pinfunction "GND_41") (pintype "bidirectional"))
      (node (ref "U1") (pin "55") (pinfunction "GND_55") (pintype "bidirectional"))
      (node (ref "U2") (pin "2") (pinfunction "GND_2") (pintype "bidirectional"))
      (node (ref "U2") (pin "37") (pinfunction "GND_37") (pintype "bidirectional"))
      (node (ref "U2") (pin "39") (pinfunction "GND_39") (pintype "bidirectional"))
      (node (ref "U3") (pin "GND") (pinfunction "GND_GND") (pintype "input"))
      (node (ref "X1") (pin "1") (pinfunction "1_1") (pintype "power_in"))
      (node (ref "X1") (pin "3") (pinfunction "3_3") (pintype "power_in"))
    )
    (net (code "55") (name "Net-(JP3-Pad1)") (class "Default")
      (node (ref "JP3") (pin "1") (pinfunction "1_1") (pintype "passive"))
      (node (ref "U3") (pin "OUT") (pinfunction "OUT_OUT") (pintype "output"))
    )
    (net (code "56") (name "VIN") (class "Default")
      (node (ref "C16") (pin "1") (pinfunction "+_1") (pintype "passive"))
      (node (ref "C17") (pin "1") (pinfunction "+_1") (pintype "passive"))
      (node (ref "IC2") (pin "8") (pinfunction "VCC2_8") (pintype "power_in"))
      (node (ref "IC3") (pin "8") (pinfunction "VCC2_8") (pintype "power_in"))
      (node (ref "JP3") (pin "3") (pinfunction "3_3") (pintype "passive"))
      (node (ref "JP4") (pin "2") (pinfunction "2_2") (pintype "passive"))
      (node (ref "U3") (pin "IN") (pinfunction "IN_IN") (pintype "input"))
      (node (ref "X1") (pin "2") (pinfunction "2_2") (pintype "power_in"))
    )
    (net (code "57") (name "unconnected-(JP8-Pad2)") (class "Default")
      (node (ref "JP8") (pin "2") (pinfunction "2_2") (pintype "passive"))
    )
    (net (code "58") (name "unconnected-(JP8-Pad3)") (class "Default")
      (node (ref "JP8") (pin "3") (pinfunction "3_3") (pintype "passive"))
    )
    (net (code "59") (name "unconnected-(JP8-Pad6)") (class "Default")
      (node (ref "JP8") (pin "6") (pinfunction "6_6") (pintype "passive"))
    )
    (net (code "60") (name "unconnected-(U1-5V_OUT-Pad1)") (class "Default")
      (node (ref "U1") (pin "1") (pinfunction "5V_OUT_1") (pintype "bidirectional"))
    )
    (net (code "61") (name "unconnected-(U1-PIN24{slash}SCK-Pad30)") (class "Default")
      (node (ref "U1") (pin "30") (pinfunction "PIN24/SCK_30") (pintype "bidirectional"))
    )
    (net (code "62") (name "unconnected-(U1-PIN25{slash}SDI-Pad31)") (class "Default")
      (node (ref "U1") (pin "31") (pinfunction "PIN25/SDI_31") (pintype "bidirectional"))
    )
    (net (code "63") (name "unconnected-(U1-PIN26{slash}SDO-Pad32)") (class "Default")
      (node (ref "U1") (pin "32") (pinfunction "PIN26/SDO_32") (pintype "bidirectional"))
    )
    (net (code "64") (name "unconnected-(U1-PIN27{slash}SS-Pad33)") (class "Default")
      (node (ref "U1") (pin "33") (pinfunction "PIN27/SS_33") (pintype "bidirectional"))
    )
    (net (code "65") (name "unconnected-(U2-5V_OUT-Pad1)") (class "Default")
      (node (ref "U2") (pin "1") (pinfunction "5V_OUT_1") (pintype "bidirectional"))
    )
  )
)
